# TEMPSENS.net
KiCad netlist of a schematic drawn in Altium Designer
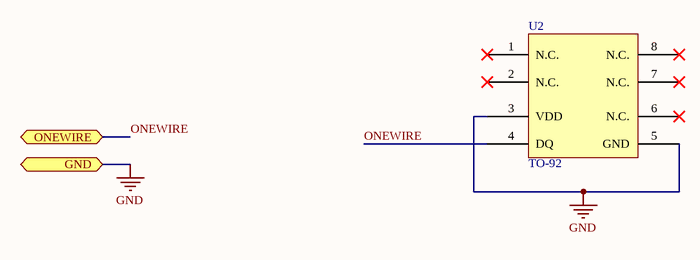
[diagram p0: TEMPSENS.SchDoc]

(export (version "E")
  (design (tool "Eeschema 10.0.6"))
  (components
    (comp (ref "U2")
      (value "TO-92")
      (footprint "DS18S20")
      (description "1-Wire Digital Thermometer")
      (fields (field (name "MANUFACTURER") "Maxim"))
      (libsource (lib "Tray 1 Expansion Board Prototype") (part "DS18S20"))
    )
  )
  (nets
    (net (code "1") (name "/ONEWIRE") (class "Default")
      (node (ref "U2") (pin "4") (pinfunction "DQ_4") (pintype "passive"))
    )
    (net (code "2") (name "GND") (class "Default")
      (node (ref "U2") (pin "3") (pinfunction "VDD_3") (pintype "passive"))
      (node (ref "U2") (pin "5") (pinfunction "GND_5") (pintype "passive"))
    )
    (net (code "3") (name "unconnected-(U2-N.C.-Pad1)") (class "Default")
      (node (ref "U2") (pin "1") (pinfunction "N.C._1") (pintype "passive+no_connect"))
    )
    (net (code "4") (name "unconnected-(U2-N.C.-Pad2)") (class "Default")
      (node (ref "U2") (pin "2") (pinfunction "N.C._2") (pintype "passive+no_connect"))
    )
    (net (code "5") (name "unconnected-(U2-N.C.-Pad6)") (class "Default")
      (node (ref "U2") (pin "6") (pinfunction "N.C._6") (pintype "passive+no_connect"))
    )
    (net (code "6") (name "unconnected-(U2-N.C.-Pad7)") (class "Default")
      (node (ref "U2") (pin "7") (pinfunction "N.C._7") (pintype "passive+no_connect"))
    )
    (net (code "7") (name "unconnected-(U2-N.C.-Pad8)") (class "Default")
      (node (ref "U2") (pin "8") (pinfunction "N.C._8") (pintype "passive+no_connect"))
    )
  )
)
